# Power.net
KiCad netlist of a schematic drawn in Altium Designer
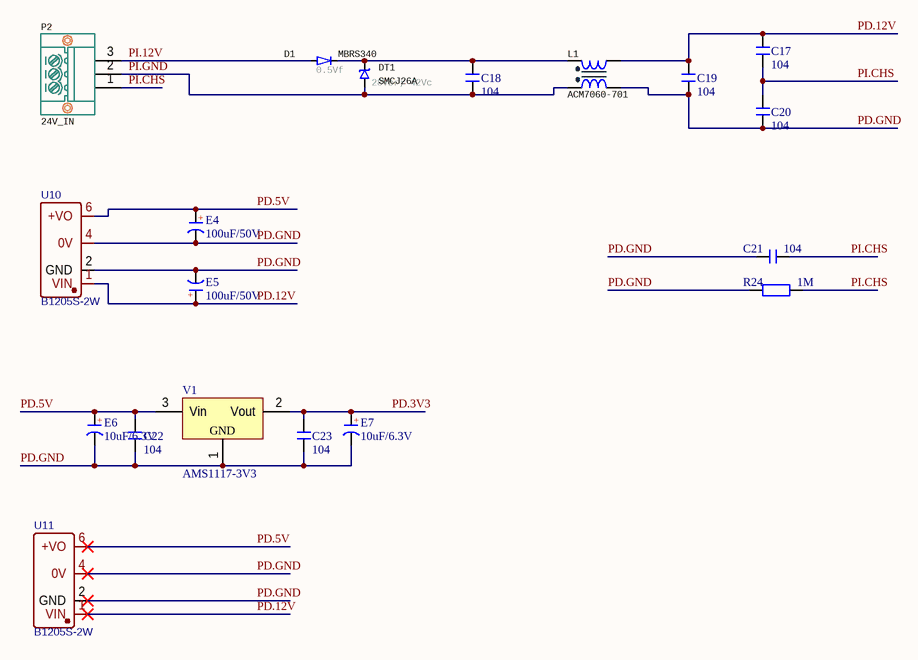
[diagram p0: Power.SchDoc]

(export (version "E")
  (design (tool "Eeschema 10.0.6"))
  (components
    (comp (ref "C17")
      (value "104")
      (footprint "C 1210")
      (description "无极性贴片电容")
      (fields (field (name "版权归属") "源创客"))
      (libsource (lib "电阻-电容-电感") (part "C"))
    )
    (comp (ref "C18")
      (value "104")
      (footprint "C 1210")
      (description "无极性贴片电容")
      (fields (field (name "版权归属") "源创客"))
      (libsource (lib "电阻-电容-电感") (part "C"))
    )
    (comp (ref "C19")
      (value "104")
      (footprint "C 1210")
      (description "无极性贴片电容")
      (fields (field (name "版权归属") "源创客"))
      (libsource (lib "电阻-电容-电感") (part "C"))
    )
    (comp (ref "C20")
      (value "104")
      (footprint "C 1210")
      (description "无极性贴片电容")
      (fields (field (name "版权归属") "源创客"))
      (libsource (lib "电阻-电容-电感") (part "C"))
    )
    (comp (ref "C21")
      (value "104")
      (footprint "C 1210")
      (description "无极性贴片电容")
      (fields (field (name "版权归属") "源创客"))
      (libsource (lib "电阻-电容-电感") (part "C"))
    )
    (comp (ref "C22")
      (value "104")
      (footprint "C 1210")
      (description "无极性贴片电容")
      (fields (field (name "版权归属") "源创客"))
      (libsource (lib "电阻-电容-电感") (part "C"))
    )
    (comp (ref "C23")
      (value "104")
      (footprint "C 1210")
      (description "无极性贴片电容")
      (fields (field (name "版权归属") "源创客"))
      (libsource (lib "电阻-电容-电感") (part "C"))
    )
    (comp (ref "D1")
      (value "MBRS340")
      (footprint "D-SMC")
      (description "D-SMC-MBRS340")
      (fields (field (name "01_INF") "0.5Vf"))
      (libsource (lib "TKAI0163WP01-01") (part "Diode"))
    )
    (comp (ref "DT1")
      (value "SMCJ26A")
      (footprint "D-SMC")
      (description "DT-SMC-SMCJ26A")
      (fields (field (name "01_INF") "28Vbr; 42Vc"))
      (libsource (lib "TKAI0163WP01-01") (part "Diode_TVS_UniDirectional"))
    )
    (comp (ref "E4")
      (value "100uF/50V")
      (footprint "CM F(10*10.2)")
      (description "贴片电解电容")
      (fields (field (name "版权归属") "源创客"))
      (libsource (lib "电阻-电容-电感") (part "C-CM"))
    )
    (comp (ref "E5")
      (value "100uF/50V")
      (footprint "CM F(10*10.2)")
      (description "贴片电解电容")
      (fields (field (name "版权归属") "源创客"))
      (libsource (lib "电阻-电容-电感") (part "C-CM"))
    )
    (comp (ref "E6")
      (value "10uF/6.3V")
      (footprint "CD A(3216)")
      (description "贴片钽电容")
      (fields (field (name "版权归属") "源创客"))
      (libsource (lib "3.1   - 电阻-电容-电感") (part "C-CD"))
    )
    (comp (ref "E7")
      (value "10uF/6.3V")
      (footprint "CD A(3216)")
      (description "贴片钽电容")
      (fields (field (name "版权归属") "源创客"))
      (libsource (lib "3.1   - 电阻-电容-电感") (part "C-CD"))
    )
    (comp (ref "L1")
      (value "ACM7060-701")
      (footprint "TDK_Choke_ACM7060")
      (description "L-ACM7060-701")
      (libsource (lib "TKAI0163WP01-01") (part "IND_CHOKE"))
    )
    (comp (ref "P2")
      (value "24V_IN")
      (footprint "C00170")
      (description "P-插装绿座_弯_针_单排_3.5_3P_紧固")
      (libsource (lib "TKAI0163WP01-01") (part "C00170_绿座_弯_针_单排_3.50_3P_紧固"))
    )
    (comp (ref "R24")
      (value "1M")
      (footprint "R 1206_L")
      (description "贴片电阻")
      (fields (field (name "版权归属") "源创客"))
      (libsource (lib "电阻-电容-电感") (part "R"))
    )
    (comp (ref "U10")
      (value "B1205S-2W")
      (footprint "B1205S-2W")
      (fields (field (name "BOM_SUPPLIER PART") "C442553") (field (name "CONTRIBUTOR") "LCSC"))
      (libsource (lib "altium-import") (part "root_2_B1205S-2W_"))
    )
    (comp (ref "U11")
      (value "B1205S-2W")
      (footprint "B1205S-2W")
      (fields (field (name "BOM_SUPPLIER PART") "C442553") (field (name "CONTRIBUTOR") "LCSC"))
      (libsource (lib "altium-import") (part "root_2_B1205S-2W_"))
    )
    (comp (ref "V1")
      (value "AMS1117-3V3")
      (footprint "SOT223_L")
      (description "三端稳压芯片")
      (fields (field (name "版权归属") "源创客"))
      (libsource (lib "IC芯片") (part "AMS1117"))
    )
  )
  (nets
    (net (code "1") (name "/PD.3V3") (class "Default")
      (node (ref "C23") (pin "1") (pinfunction "1_1") (pintype "passive"))
      (node (ref "E7") (pin "1") (pinfunction "A_1") (pintype "passive"))
      (node (ref "V1") (pin "2") (pinfunction "Vout_2") (pintype "passive"))
    )
    (net (code "2") (name "/PD.5V") (class "Default")
      (node (ref "C22") (pin "1") (pinfunction "1_1") (pintype "passive"))
      (node (ref "E4") (pin "1") (pinfunction "A_1") (pintype "passive"))
      (node (ref "E6") (pin "1") (pinfunction "A_1") (pintype "passive"))
      (node (ref "U10") (pin "6") (pinfunction "+VO_6") (pintype "passive"))
      (node (ref "U11") (pin "6") (pinfunction "+VO_6") (pintype "passive"))
      (node (ref "V1") (pin "3") (pinfunction "Vin_3") (pintype "passive"))
    )
    (net (code "3") (name "/PD.12V") (class "Default")
      (node (ref "C17") (pin "1") (pinfunction "1_1") (pintype "passive"))
      (node (ref "C19") (pin "2") (pinfunction "2_2") (pintype "passive"))
      (node (ref "E5") (pin "1") (pinfunction "A_1") (pintype "passive"))
      (node (ref "L1") (pin "A2") (pinfunction "A2_A2") (pintype "passive"))
      (node (ref "U10") (pin "1") (pinfunction "VIN_1") (pintype "passive"))
      (node (ref "U11") (pin "1") (pinfunction "VIN_1") (pintype "passive"))
    )
    (net (code "4") (name "/PD.GND") (class "Default")
      (node (ref "C19") (pin "1") (pinfunction "1_1") (pintype "passive"))
      (node (ref "C20") (pin "2") (pinfunction "2_2") (pintype "passive"))
      (node (ref "C21") (pin "1") (pinfunction "1_1") (pintype "passive"))
      (node (ref "C22") (pin "2") (pinfunction "2_2") (pintype "passive"))
      (node (ref "C23") (pin "2") (pinfunction "2_2") (pintype "passive"))
      (node (ref "E4") (pin "2") (pinfunction "K_2") (pintype "passive"))
      (node (ref "E5") (pin "2") (pinfunction "K_2") (pintype "passive"))
      (node (ref "E6") (pin "2") (pinfunction "K_2") (pintype "passive"))
      (node (ref "E7") (pin "2") (pinfunction "K_2") (pintype "passive"))
      (node (ref "L1") (pin "B2") (pinfunction "B2_B2") (pintype "passive"))
      (node (ref "R24") (pin "1") (pinfunction "1_1") (pintype "passive"))
      (node (ref "U10") (pin "2") (pinfunction "GND_2") (pintype "passive"))
      (node (ref "U10") (pin "4") (pinfunction "0V_4") (pintype "passive"))
      (node (ref "U11") (pin "2") (pinfunction "GND_2") (pintype "passive"))
      (node (ref "U11") (pin "4") (pinfunction "0V_4") (pintype "passive"))
      (node (ref "V1") (pin "1") (pinfunction "GND_1") (pintype "passive"))
    )
    (net (code "5") (name "/PI.12V") (class "Default")
      (node (ref "D1") (pin "1") (pinfunction "1_1") (pintype "passive"))
      (node (ref "P2") (pin "3") (pinfunction "3_3") (pintype "passive"))
    )
    (net (code "6") (name "/PI.CHS") (class "Default")
      (node (ref "C17") (pin "2") (pinfunction "2_2") (pintype "passive"))
      (node (ref "C20") (pin "1") (pinfunction "1_1") (pintype "passive"))
      (node (ref "C21") (pin "2") (pinfunction "2_2") (pintype "passive"))
      (node (ref "P2") (pin "1") (pinfunction "1_1") (pintype "passive"))
      (node (ref "R24") (pin "2") (pinfunction "2_2") (pintype "passive"))
    )
    (net (code "7") (name "/PI.GND") (class "Default")
      (node (ref "C18") (pin "1") (pinfunction "1_1") (pintype "passive"))
      (node (ref "DT1") (pin "1") (pinfunction "1_1") (pintype "passive"))
      (node (ref "L1") (pin "B1") (pinfunction "B1_B1") (pintype "passive"))
      (node (ref "P2") (pin "2") (pinfunction "2_2") (pintype "passive"))
    )
    (net (code "8") (name "Net-(C18-Pad2)") (class "Default")
      (node (ref "C18") (pin "2") (pinfunction "2_2") (pintype "passive"))
      (node (ref "D1") (pin "2") (pinfunction "2_2") (pintype "passive"))
      (node (ref "DT1") (pin "2") (pinfunction "2_2") (pintype "passive"))
      (node (ref "L1") (pin "A1") (pinfunction "A1_A1") (pintype "passive"))
    )
  )
)
